# Connectors.net
KiCad netlist of a schematic drawn in Altium Designer
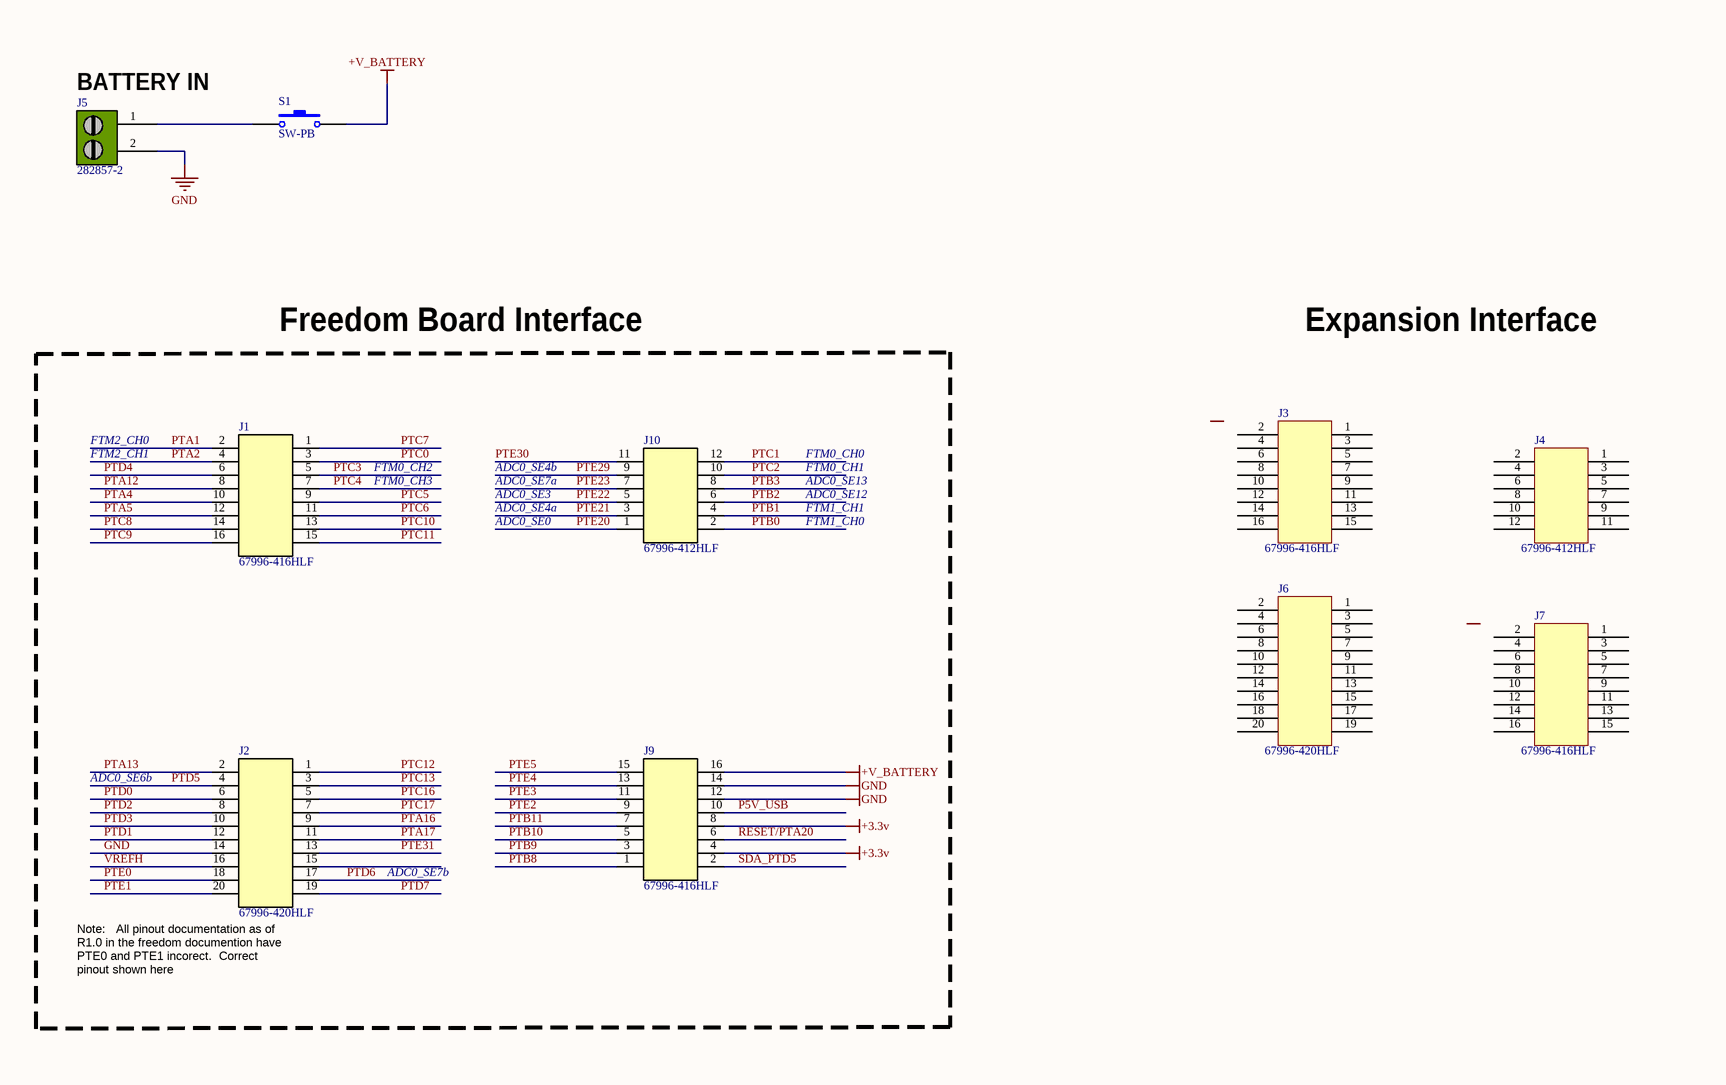
[diagram p0: Connectors.SchDoc, top left]
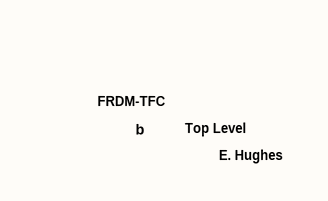
[diagram p1: Connectors.SchDoc, bottom right]

(export (version "E")
  (design (tool "Eeschema 10.0.6"))
  (components
    (comp (ref "J1")
      (value "67996-416HLF")
      (footprint "67996-416HLF")
      (description "CONN HEADER 16POS .100 STR TIN")
      (fields (field (name "MANUFACTURER") "FCI"))
      (libsource (lib "eConnector") (part "67996-416HLF"))
    )
    (comp (ref "J2")
      (value "67996-420HLF")
      (footprint "67996-420HLF")
      (description "CONN HEADER 20POS .100 STR TIN")
      (fields (field (name "MANUFACTURER") "FCI"))
      (libsource (lib "eConnector") (part "67996-420HLF"))
    )
    (comp (ref "J3")
      (value "67996-416HLF")
      (footprint "67996-416HLF")
      (description "CONN HEADER 16POS .100 STR TIN")
      (libsource (lib "Amphenol_Connectors") (part "67996-416HLF"))
    )
    (comp (ref "J4")
      (value "67996-412HLF")
      (footprint "67996-412HLF")
      (description "CONN HEADER 12POS .100 STR TIN")
      (libsource (lib "Amphenol_Connectors") (part "67996-412HLF"))
    )
    (comp (ref "J5")
      (value "282857-2")
      (footprint "282857-2")
      (description "TERM BLOCK 2POS SIDE ENT 5.08MM")
      (fields (field (name "MANUFACTURER") "TE Connectivity") (field (name "VOLTAGE") "300V"))
      (libsource (lib "eConnector") (part "282857-2"))
    )
    (comp (ref "J6")
      (value "67996-420HLF")
      (footprint "67996-420HLF")
      (description "CONN HEADER 20POS .100 STR TIN")
      (libsource (lib "Amphenol_Connectors") (part "67996-420HLF"))
    )
    (comp (ref "J7")
      (value "67996-416HLF")
      (footprint "67996-416HLF")
      (description "CONN HEADER 16POS .100 STR TIN")
      (libsource (lib "Amphenol_Connectors") (part "67996-416HLF"))
    )
    (comp (ref "J9")
      (value "67996-416HLF")
      (footprint "67996-416HLF")
      (description "CONN HEADER 16POS .100 STR TIN")
      (fields (field (name "MANUFACTURER") "FCI"))
      (libsource (lib "") (part "67996-416HLF_1"))
    )
    (comp (ref "J10")
      (value "67996-412HLF")
      (footprint "67996-412HLF")
      (description "CONN HEADER 12POS .100 STR TIN")
      (fields (field (name "MANUFACTURER") "FCI"))
      (libsource (lib "eConnector") (part "67996-412HLF"))
    )
    (comp (ref "S1")
      (value "SW-PB")
      (footprint "SPST-2")
      (description "Switch")
      (fields (field (name "PUBLISHER") "Altium Limited"))
      (libsource (lib "Miscellaneous Devices") (part "SW-PB"))
    )
  )
  (nets
    (net (code "1") (name "+3.3v") (class "Default")
      (node (ref "J9") (pin "4") (pinfunction "4_4") (pintype "passive"))
      (node (ref "J9") (pin "8") (pinfunction "8_8") (pintype "passive"))
    )
    (net (code "2") (name "+V_BATTERY") (class "Default")
      (node (ref "J9") (pin "16") (pinfunction "16_16") (pintype "passive"))
      (node (ref "S1") (pin "2") (pinfunction "2_2") (pintype "passive"))
    )
    (net (code "3") (name "/P5V_USB") (class "Default")
      (node (ref "J9") (pin "10") (pinfunction "10_10") (pintype "passive"))
    )
    (net (code "4") (name "/PTA1") (class "Default")
      (node (ref "J1") (pin "2") (pinfunction "2_2") (pintype "passive"))
    )
    (net (code "5") (name "/PTA2") (class "Default")
      (node (ref "J1") (pin "4") (pinfunction "4_4") (pintype "passive"))
    )
    (net (code "6") (name "/PTA4") (class "Default")
      (node (ref "J1") (pin "10") (pinfunction "10_10") (pintype "passive"))
    )
    (net (code "7") (name "/PTA5") (class "Default")
      (node (ref "J1") (pin "12") (pinfunction "12_12") (pintype "passive"))
    )
    (net (code "8") (name "/PTA12") (class "Default")
      (node (ref "J1") (pin "8") (pinfunction "8_8") (pintype "passive"))
    )
    (net (code "9") (name "/PTA13") (class "Default")
      (node (ref "J2") (pin "2") (pinfunction "2_2") (pintype "passive"))
    )
    (net (code "10") (name "/PTA16") (class "Default")
      (node (ref "J2") (pin "9") (pinfunction "9_9") (pintype "passive"))
    )
    (net (code "11") (name "/PTA17") (class "Default")
      (node (ref "J2") (pin "11") (pinfunction "11_11") (pintype "passive"))
    )
    (net (code "12") (name "/PTB0") (class "Default")
      (node (ref "J10") (pin "2") (pinfunction "2_2") (pintype "passive"))
    )
    (net (code "13") (name "/PTB1") (class "Default")
      (node (ref "J10") (pin "4") (pinfunction "4_4") (pintype "passive"))
    )
    (net (code "14") (name "/PTB2") (class "Default")
      (node (ref "J10") (pin "6") (pinfunction "6_6") (pintype "passive"))
    )
    (net (code "15") (name "/PTB3") (class "Default")
      (node (ref "J10") (pin "8") (pinfunction "8_8") (pintype "passive"))
    )
    (net (code "16") (name "/PTB8") (class "Default")
      (node (ref "J9") (pin "1") (pinfunction "1_1") (pintype "passive"))
    )
    (net (code "17") (name "/PTB9") (class "Default")
      (node (ref "J9") (pin "3") (pinfunction "3_3") (pintype "passive"))
    )
    (net (code "18") (name "/PTB10") (class "Default")
      (node (ref "J9") (pin "5") (pinfunction "5_5") (pintype "passive"))
    )
    (net (code "19") (name "/PTB11") (class "Default")
      (node (ref "J9") (pin "7") (pinfunction "7_7") (pintype "passive"))
    )
    (net (code "20") (name "/PTC0") (class "Default")
      (node (ref "J1") (pin "3") (pinfunction "3_3") (pintype "passive"))
    )
    (net (code "21") (name "/PTC1") (class "Default")
      (node (ref "J10") (pin "12") (pinfunction "12_12") (pintype "passive"))
    )
    (net (code "22") (name "/PTC2") (class "Default")
      (node (ref "J10") (pin "10") (pinfunction "10_10") (pintype "passive"))
    )
    (net (code "23") (name "/PTC3") (class "Default")
      (node (ref "J1") (pin "5") (pinfunction "5_5") (pintype "passive"))
    )
    (net (code "24") (name "/PTC4") (class "Default")
      (node (ref "J1") (pin "7") (pinfunction "7_7") (pintype "passive"))
    )
    (net (code "25") (name "/PTC5") (class "Default")
      (node (ref "J1") (pin "9") (pinfunction "9_9") (pintype "passive"))
    )
    (net (code "26") (name "/PTC6") (class "Default")
      (node (ref "J1") (pin "11") (pinfunction "11_11") (pintype "passive"))
    )
    (net (code "27") (name "/PTC7") (class "Default")
      (node (ref "J1") (pin "1") (pinfunction "1_1") (pintype "passive"))
    )
    (net (code "28") (name "/PTC8") (class "Default")
      (node (ref "J1") (pin "14") (pinfunction "14_14") (pintype "passive"))
    )
    (net (code "29") (name "/PTC9") (class "Default")
      (node (ref "J1") (pin "16") (pinfunction "16_16") (pintype "passive"))
    )
    (net (code "30") (name "/PTC10") (class "Default")
      (node (ref "J1") (pin "13") (pinfunction "13_13") (pintype "passive"))
    )
    (net (code "31") (name "/PTC11") (class "Default")
      (node (ref "J1") (pin "15") (pinfunction "15_15") (pintype "passive"))
    )
    (net (code "32") (name "/PTC12") (class "Default")
      (node (ref "J2") (pin "1") (pinfunction "1_1") (pintype "passive"))
    )
    (net (code "33") (name "/PTC13") (class "Default")
      (node (ref "J2") (pin "3") (pinfunction "3_3") (pintype "passive"))
    )
    (net (code "34") (name "/PTC16") (class "Default")
      (node (ref "J2") (pin "5") (pinfunction "5_5") (pintype "passive"))
    )
    (net (code "35") (name "/PTC17") (class "Default")
      (node (ref "J2") (pin "7") (pinfunction "7_7") (pintype "passive"))
    )
    (net (code "36") (name "/PTD0") (class "Default")
      (node (ref "J2") (pin "6") (pinfunction "6_6") (pintype "passive"))
    )
    (net (code "37") (name "/PTD1") (class "Default")
      (node (ref "J2") (pin "12") (pinfunction "12_12") (pintype "passive"))
    )
    (net (code "38") (name "/PTD2") (class "Default")
      (node (ref "J2") (pin "8") (pinfunction "8_8") (pintype "passive"))
    )
    (net (code "39") (name "/PTD3") (class "Default")
      (node (ref "J2") (pin "10") (pinfunction "10_10") (pintype "passive"))
    )
    (net (code "40") (name "/PTD4") (class "Default")
      (node (ref "J1") (pin "6") (pinfunction "6_6") (pintype "passive"))
    )
    (net (code "41") (name "/PTD5") (class "Default")
      (node (ref "J2") (pin "4") (pinfunction "4_4") (pintype "passive"))
    )
    (net (code "42") (name "/PTD6") (class "Default")
      (node (ref "J2") (pin "17") (pinfunction "17_17") (pintype "passive"))
    )
    (net (code "43") (name "/PTD7") (class "Default")
      (node (ref "J2") (pin "19") (pinfunction "19_19") (pintype "passive"))
    )
    (net (code "44") (name "/PTE0") (class "Default")
      (node (ref "J2") (pin "18") (pinfunction "18_18") (pintype "passive"))
    )
    (net (code "45") (name "/PTE1") (class "Default")
      (node (ref "J2") (pin "20") (pinfunction "20_20") (pintype "passive"))
    )
    (net (code "46") (name "/PTE2") (class "Default")
      (node (ref "J9") (pin "9") (pinfunction "9_9") (pintype "passive"))
    )
    (net (code "47") (name "/PTE3") (class "Default")
      (node (ref "J9") (pin "11") (pinfunction "11_11") (pintype "passive"))
    )
    (net (code "48") (name "/PTE4") (class "Default")
      (node (ref "J9") (pin "13") (pinfunction "13_13") (pintype "passive"))
    )
    (net (code "49") (name "/PTE5") (class "Default")
      (node (ref "J9") (pin "15") (pinfunction "15_15") (pintype "passive"))
    )
    (net (code "50") (name "/PTE20") (class "Default")
      (node (ref "J10") (pin "1") (pinfunction "1_1") (pintype "passive"))
    )
    (net (code "51") (name "/PTE21") (class "Default")
      (node (ref "J10") (pin "3") (pinfunction "3_3") (pintype "passive"))
    )
    (net (code "52") (name "/PTE22") (class "Default")
      (node (ref "J10") (pin "5") (pinfunction "5_5") (pintype "passive"))
    )
    (net (code "53") (name "/PTE23") (class "Default")
      (node (ref "J10") (pin "7") (pinfunction "7_7") (pintype "passive"))
    )
    (net (code "54") (name "/PTE29") (class "Default")
      (node (ref "J10") (pin "9") (pinfunction "9_9") (pintype "passive"))
    )
    (net (code "55") (name "/PTE30") (class "Default")
      (node (ref "J10") (pin "11") (pinfunction "11_11") (pintype "passive"))
    )
    (net (code "56") (name "/PTE31") (class "Default")
      (node (ref "J2") (pin "13") (pinfunction "13_13") (pintype "passive"))
    )
    (net (code "57") (name "/RESET{slash}PTA20") (class "Default")
      (node (ref "J9") (pin "6") (pinfunction "6_6") (pintype "passive"))
    )
    (net (code "58") (name "/SDA_PTD5") (class "Default")
      (node (ref "J9") (pin "2") (pinfunction "2_2") (pintype "passive"))
    )
    (net (code "59") (name "/VREFH") (class "Default")
      (node (ref "J2") (pin "16") (pinfunction "16_16") (pintype "passive"))
    )
    (net (code "60") (name "GND") (class "Default")
      (node (ref "J2") (pin "14") (pinfunction "14_14") (pintype "passive"))
      (node (ref "J5") (pin "2") (pinfunction "2_2") (pintype "passive"))
      (node (ref "J9") (pin "12") (pinfunction "12_12") (pintype "passive"))
      (node (ref "J9") (pin "14") (pinfunction "14_14") (pintype "passive"))
    )
    (net (code "61") (name "Net-(J5-Pad1)") (class "Default")
      (node (ref "J5") (pin "1") (pinfunction "1_1") (pintype "passive"))
      (node (ref "S1") (pin "1") (pinfunction "1_1") (pintype "passive"))
    )
    (net (code "62") (name "unconnected-(J2-Pad15)") (class "Default")
      (node (ref "J2") (pin "15") (pinfunction "15_15") (pintype "passive"))
    )
    (net (code "63") (name "unconnected-(J3-Pad1)") (class "Default")
      (node (ref "J3") (pin "1") (pinfunction "1_1") (pintype "passive"))
    )
    (net (code "64") (name "unconnected-(J3-Pad2)") (class "Default")
      (node (ref "J3") (pin "2") (pinfunction "2_2") (pintype "passive"))
    )
    (net (code "65") (name "unconnected-(J3-Pad3)") (class "Default")
      (node (ref "J3") (pin "3") (pinfunction "3_3") (pintype "passive"))
    )
    (net (code "66") (name "unconnected-(J3-Pad4)") (class "Default")
      (node (ref "J3") (pin "4") (pinfunction "4_4") (pintype "passive"))
    )
    (net (code "67") (name "unconnected-(J3-Pad5)") (class "Default")
      (node (ref "J3") (pin "5") (pinfunction "5_5") (pintype "passive"))
    )
    (net (code "68") (name "unconnected-(J3-Pad6)") (class "Default")
      (node (ref "J3") (pin "6") (pinfunction "6_6") (pintype "passive"))
    )
    (net (code "69") (name "unconnected-(J3-Pad7)") (class "Default")
      (node (ref "J3") (pin "7") (pinfunction "7_7") (pintype "passive"))
    )
    (net (code "70") (name "unconnected-(J3-Pad8)") (class "Default")
      (node (ref "J3") (pin "8") (pinfunction "8_8") (pintype "passive"))
    )
    (net (code "71") (name "unconnected-(J3-Pad9)") (class "Default")
      (node (ref "J3") (pin "9") (pinfunction "9_9") (pintype "passive"))
    )
    (net (code "72") (name "unconnected-(J3-Pad10)") (class "Default")
      (node (ref "J3") (pin "10") (pinfunction "10_10") (pintype "passive"))
    )
    (net (code "73") (name "unconnected-(J3-Pad11)") (class "Default")
      (node (ref "J3") (pin "11") (pinfunction "11_11") (pintype "passive"))
    )
    (net (code "74") (name "unconnected-(J3-Pad12)") (class "Default")
      (node (ref "J3") (pin "12") (pinfunction "12_12") (pintype "passive"))
    )
    (net (code "75") (name "unconnected-(J3-Pad13)") (class "Default")
      (node (ref "J3") (pin "13") (pinfunction "13_13") (pintype "passive"))
    )
    (net (code "76") (name "unconnected-(J3-Pad14)") (class "Default")
      (node (ref "J3") (pin "14") (pinfunction "14_14") (pintype "passive"))
    )
    (net (code "77") (name "unconnected-(J3-Pad15)") (class "Default")
      (node (ref "J3") (pin "15") (pinfunction "15_15") (pintype "passive"))
    )
    (net (code "78") (name "unconnected-(J3-Pad16)") (class "Default")
      (node (ref "J3") (pin "16") (pinfunction "16_16") (pintype "passive"))
    )
    (net (code "79") (name "unconnected-(J4-Pad1)") (class "Default")
      (node (ref "J4") (pin "1") (pinfunction "1_1") (pintype "passive"))
    )
    (net (code "80") (name "unconnected-(J4-Pad2)") (class "Default")
      (node (ref "J4") (pin "2") (pinfunction "2_2") (pintype "passive"))
    )
    (net (code "81") (name "unconnected-(J4-Pad3)") (class "Default")
      (node (ref "J4") (pin "3") (pinfunction "3_3") (pintype "passive"))
    )
    (net (code "82") (name "unconnected-(J4-Pad4)") (class "Default")
      (node (ref "J4") (pin "4") (pinfunction "4_4") (pintype "passive"))
    )
    (net (code "83") (name "unconnected-(J4-Pad5)") (class "Default")
      (node (ref "J4") (pin "5") (pinfunction "5_5") (pintype "passive"))
    )
    (net (code "84") (name "unconnected-(J4-Pad6)") (class "Default")
      (node (ref "J4") (pin "6") (pinfunction "6_6") (pintype "passive"))
    )
    (net (code "85") (name "unconnected-(J4-Pad7)") (class "Default")
      (node (ref "J4") (pin "7") (pinfunction "7_7") (pintype "passive"))
    )
    (net (code "86") (name "unconnected-(J4-Pad8)") (class "Default")
      (node (ref "J4") (pin "8") (pinfunction "8_8") (pintype "passive"))
    )
    (net (code "87") (name "unconnected-(J4-Pad9)") (class "Default")
      (node (ref "J4") (pin "9") (pinfunction "9_9") (pintype "passive"))
    )
    (net (code "88") (name "unconnected-(J4-Pad10)") (class "Default")
      (node (ref "J4") (pin "10") (pinfunction "10_10") (pintype "passive"))
    )
    (net (code "89") (name "unconnected-(J4-Pad11)") (class "Default")
      (node (ref "J4") (pin "11") (pinfunction "11_11") (pintype "passive"))
    )
    (net (code "90") (name "unconnected-(J4-Pad12)") (class "Default")
      (node (ref "J4") (pin "12") (pinfunction "12_12") (pintype "passive"))
    )
    (net (code "91") (name "unconnected-(J6-Pad1)") (class "Default")
      (node (ref "J6") (pin "1") (pinfunction "1_1") (pintype "passive"))
    )
    (net (code "92") (name "unconnected-(J6-Pad2)") (class "Default")
      (node (ref "J6") (pin "2") (pinfunction "2_2") (pintype "passive"))
    )
    (net (code "93") (name "unconnected-(J6-Pad3)") (class "Default")
      (node (ref "J6") (pin "3") (pinfunction "3_3") (pintype "passive"))
    )
    (net (code "94") (name "unconnected-(J6-Pad4)") (class "Default")
      (node (ref "J6") (pin "4") (pinfunction "4_4") (pintype "passive"))
    )
    (net (code "95") (name "unconnected-(J6-Pad5)") (class "Default")
      (node (ref "J6") (pin "5") (pinfunction "5_5") (pintype "passive"))
    )
    (net (code "96") (name "unconnected-(J6-Pad6)") (class "Default")
      (node (ref "J6") (pin "6") (pinfunction "6_6") (pintype "passive"))
    )
    (net (code "97") (name "unconnected-(J6-Pad7)") (class "Default")
      (node (ref "J6") (pin "7") (pinfunction "7_7") (pintype "passive"))
    )
    (net (code "98") (name "unconnected-(J6-Pad8)") (class "Default")
      (node (ref "J6") (pin "8") (pinfunction "8_8") (pintype "passive"))
    )
    (net (code "99") (name "unconnected-(J6-Pad9)") (class "Default")
      (node (ref "J6") (pin "9") (pinfunction "9_9") (pintype "passive"))
    )
    (net (code "100") (name "unconnected-(J6-Pad10)") (class "Default")
      (node (ref "J6") (pin "10") (pinfunction "10_10") (pintype "passive"))
    )
    (net (code "101") (name "unconnected-(J6-Pad11)") (class "Default")
      (node (ref "J6") (pin "11") (pinfunction "11_11") (pintype "passive"))
    )
    (net (code "102") (name "unconnected-(J6-Pad12)") (class "Default")
      (node (ref "J6") (pin "12") (pinfunction "12_12") (pintype "passive"))
    )
    (net (code "103") (name "unconnected-(J6-Pad13)") (class "Default")
      (node (ref "J6") (pin "13") (pinfunction "13_13") (pintype "passive"))
    )
    (net (code "104") (name "unconnected-(J6-Pad14)") (class "Default")
      (node (ref "J6") (pin "14") (pinfunction "14_14") (pintype "passive"))
    )
    (net (code "105") (name "unconnected-(J6-Pad15)") (class "Default")
      (node (ref "J6") (pin "15") (pinfunction "15_15") (pintype "passive"))
    )
    (net (code "106") (name "unconnected-(J6-Pad16)") (class "Default")
      (node (ref "J6") (pin "16") (pinfunction "16_16") (pintype "passive"))
    )
    (net (code "107") (name "unconnected-(J6-Pad17)") (class "Default")
      (node (ref "J6") (pin "17") (pinfunction "17_17") (pintype "passive"))
    )
    (net (code "108") (name "unconnected-(J6-Pad18)") (class "Default")
      (node (ref "J6") (pin "18") (pinfunction "18_18") (pintype "passive"))
    )
    (net (code "109") (name "unconnected-(J6-Pad19)") (class "Default")
      (node (ref "J6") (pin "19") (pinfunction "19_19") (pintype "passive"))
    )
    (net (code "110") (name "unconnected-(J6-Pad20)") (class "Default")
      (node (ref "J6") (pin "20") (pinfunction "20_20") (pintype "passive"))
    )
    (net (code "111") (name "unconnected-(J7-Pad1)") (class "Default")
      (node (ref "J7") (pin "1") (pinfunction "1_1") (pintype "passive"))
    )
    (net (code "112") (name "unconnected-(J7-Pad2)") (class "Default")
      (node (ref "J7") (pin "2") (pinfunction "2_2") (pintype "passive"))
    )
    (net (code "113") (name "unconnected-(J7-Pad3)") (class "Default")
      (node (ref "J7") (pin "3") (pinfunction "3_3") (pintype "passive"))
    )
    (net (code "114") (name "unconnected-(J7-Pad4)") (class "Default")
      (node (ref "J7") (pin "4") (pinfunction "4_4") (pintype "passive"))
    )
    (net (code "115") (name "unconnected-(J7-Pad5)") (class "Default")
      (node (ref "J7") (pin "5") (pinfunction "5_5") (pintype "passive"))
    )
    (net (code "116") (name "unconnected-(J7-Pad6)") (class "Default")
      (node (ref "J7") (pin "6") (pinfunction "6_6") (pintype "passive"))
    )
    (net (code "117") (name "unconnected-(J7-Pad7)") (class "Default")
      (node (ref "J7") (pin "7") (pinfunction "7_7") (pintype "passive"))
    )
    (net (code "118") (name "unconnected-(J7-Pad8)") (class "Default")
      (node (ref "J7") (pin "8") (pinfunction "8_8") (pintype "passive"))
    )
    (net (code "119") (name "unconnected-(J7-Pad9)") (class "Default")
      (node (ref "J7") (pin "9") (pinfunction "9_9") (pintype "passive"))
    )
    (net (code "120") (name "unconnected-(J7-Pad10)") (class "Default")
      (node (ref "J7") (pin "10") (pinfunction "10_10") (pintype "passive"))
    )
    (net (code "121") (name "unconnected-(J7-Pad11)") (class "Default")
      (node (ref "J7") (pin "11") (pinfunction "11_11") (pintype "passive"))
    )
    (net (code "122") (name "unconnected-(J7-Pad12)") (class "Default")
      (node (ref "J7") (pin "12") (pinfunction "12_12") (pintype "passive"))
    )
    (net (code "123") (name "unconnected-(J7-Pad13)") (class "Default")
      (node (ref "J7") (pin "13") (pinfunction "13_13") (pintype "passive"))
    )
    (net (code "124") (name "unconnected-(J7-Pad14)") (class "Default")
      (node (ref "J7") (pin "14") (pinfunction "14_14") (pintype "passive"))
    )
    (net (code "125") (name "unconnected-(J7-Pad15)") (class "Default")
      (node (ref "J7") (pin "15") (pinfunction "15_15") (pintype "passive"))
    )
    (net (code "126") (name "unconnected-(J7-Pad16)") (class "Default")
      (node (ref "J7") (pin "16") (pinfunction "16_16") (pintype "passive"))
    )
  )
)
